# USB_Audio.net
KiCad netlist of a schematic drawn in Altium Designer
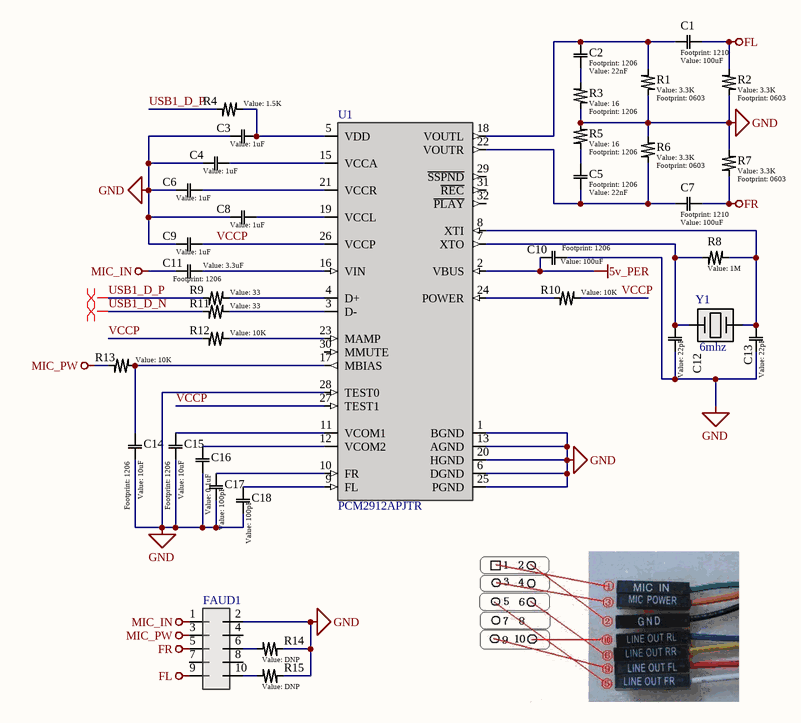
[diagram p0: USB_Audio.SchDoc]

(export (version "E")
  (design (tool "Eeschema 10.0.6"))
  (components
    (comp (ref "C1")
      (value "100uF")
      (footprint "1210")
      (fields
        (field (name "VOLTAGE") ">10V")
        (field (name "TOLERANCE") "10%")
        (field (name "Comment") "Generic Capacitor")
      )
      (libsource (lib "Capacitors") (part "Generic Capacitor"))
    )
    (comp (ref "C2")
      (value "22nF")
      (footprint "1206")
      (fields
        (field (name "VOLTAGE") ">10V")
        (field (name "TOLERANCE") "10%")
        (field (name "Comment") "Generic Capacitor")
      )
      (libsource (lib "Capacitors") (part "Generic Capacitor"))
    )
    (comp (ref "C3")
      (value "1uF")
      (footprint "0603")
      (fields
        (field (name "VOLTAGE") ">10V")
        (field (name "TOLERANCE") "10%")
        (field (name "Comment") "Generic Capacitor")
      )
      (libsource (lib "Capacitors") (part "Generic Capacitor"))
    )
    (comp (ref "C4")
      (value "1uF")
      (footprint "0603")
      (fields
        (field (name "VOLTAGE") ">10V")
        (field (name "TOLERANCE") "10%")
        (field (name "Comment") "Generic Capacitor")
      )
      (libsource (lib "Capacitors") (part "Generic Capacitor"))
    )
    (comp (ref "C5")
      (value "22nF")
      (footprint "1206")
      (fields
        (field (name "VOLTAGE") ">10V")
        (field (name "TOLERANCE") "10%")
        (field (name "Comment") "Generic Capacitor")
      )
      (libsource (lib "Capacitors") (part "Generic Capacitor"))
    )
    (comp (ref "C6")
      (value "1uF")
      (footprint "0603")
      (fields
        (field (name "VOLTAGE") ">10V")
        (field (name "TOLERANCE") "10%")
        (field (name "Comment") "Generic Capacitor")
      )
      (libsource (lib "Capacitors") (part "Generic Capacitor"))
    )
    (comp (ref "C7")
      (value "100uF")
      (footprint "1210")
      (fields
        (field (name "VOLTAGE") ">10V")
        (field (name "TOLERANCE") "10%")
        (field (name "Comment") "Generic Capacitor")
      )
      (libsource (lib "Capacitors") (part "Generic Capacitor"))
    )
    (comp (ref "C8")
      (value "1uF")
      (footprint "0603")
      (fields
        (field (name "VOLTAGE") ">10V")
        (field (name "TOLERANCE") "10%")
        (field (name "Comment") "Generic Capacitor")
      )
      (libsource (lib "Capacitors") (part "Generic Capacitor"))
    )
    (comp (ref "C9")
      (value "1uF")
      (footprint "0603")
      (fields
        (field (name "VOLTAGE") ">10V")
        (field (name "TOLERANCE") "10%")
        (field (name "Comment") "Generic Capacitor")
      )
      (libsource (lib "Capacitors") (part "Generic Capacitor"))
    )
    (comp (ref "C10")
      (value "100uF")
      (footprint "1206")
      (fields
        (field (name "VOLTAGE") ">10V")
        (field (name "TOLERANCE") "10%")
        (field (name "Comment") "Generic Capacitor")
      )
      (libsource (lib "Capacitors") (part "Generic Capacitor"))
    )
    (comp (ref "C11")
      (value "3.3uF")
      (footprint "1206")
      (fields
        (field (name "VOLTAGE") ">10V")
        (field (name "TOLERANCE") "10%")
        (field (name "Comment") "Generic Capacitor")
      )
      (libsource (lib "Capacitors") (part "Generic Capacitor"))
    )
    (comp (ref "C12")
      (value "22pF")
      (footprint "0603")
      (fields
        (field (name "VOLTAGE") ">10V")
        (field (name "TOLERANCE") "10%")
        (field (name "Comment") "Generic Capacitor")
      )
      (libsource (lib "Capacitors") (part "Generic Capacitor"))
    )
    (comp (ref "C13")
      (value "22pF")
      (footprint "0603")
      (fields
        (field (name "VOLTAGE") ">10V")
        (field (name "TOLERANCE") "10%")
        (field (name "Comment") "Generic Capacitor")
      )
      (libsource (lib "Capacitors") (part "Generic Capacitor"))
    )
    (comp (ref "C14")
      (value "10uF")
      (footprint "1206")
      (fields
        (field (name "VOLTAGE") ">10V")
        (field (name "TOLERANCE") "10%")
        (field (name "Comment") "Generic Capacitor")
      )
      (libsource (lib "Capacitors") (part "Generic Capacitor"))
    )
    (comp (ref "C15")
      (value "10uF")
      (footprint "1206")
      (fields
        (field (name "VOLTAGE") ">10V")
        (field (name "TOLERANCE") "10%")
        (field (name "Comment") "Generic Capacitor")
      )
      (libsource (lib "Capacitors") (part "Generic Capacitor"))
    )
    (comp (ref "C16")
      (value "0.1uF")
      (footprint "0603")
      (fields
        (field (name "VOLTAGE") ">10V")
        (field (name "TOLERANCE") "10%")
        (field (name "Comment") "Generic Capacitor")
      )
      (libsource (lib "Capacitors") (part "Generic Capacitor"))
    )
    (comp (ref "C17")
      (value "100pF")
      (footprint "0603")
      (fields
        (field (name "VOLTAGE") ">10V")
        (field (name "TOLERANCE") "10%")
        (field (name "Comment") "Generic Capacitor")
      )
      (libsource (lib "Capacitors") (part "Generic Capacitor"))
    )
    (comp (ref "C18")
      (value "100pF")
      (footprint "0603")
      (fields
        (field (name "VOLTAGE") ">10V")
        (field (name "TOLERANCE") "10%")
        (field (name "Comment") "Generic Capacitor")
      )
      (libsource (lib "Capacitors") (part "Generic Capacitor"))
    )
    (comp (ref "FAUD1")
      (value "10pinMobo")
      (footprint "10pinMobo")
      (description "10pin motherboard jack")
      (libsource (lib "Connectors") (part "10pinMobo"))
    )
    (comp (ref "R1")
      (value "3.3K")
      (footprint "0603")
      (fields
        (field (name "TOLERANCE") "1%")
        (field (name "POWER") "1/10W")
        (field (name "Comment") "Generic Resistor")
      )
      (libsource (lib "Resistors") (part "Generic Resistor"))
    )
    (comp (ref "R2")
      (value "3.3K")
      (footprint "0603")
      (fields
        (field (name "TOLERANCE") "1%")
        (field (name "POWER") "1/10W")
        (field (name "Comment") "Generic Resistor")
      )
      (libsource (lib "Resistors") (part "Generic Resistor"))
    )
    (comp (ref "R3")
      (value "16")
      (footprint "1206")
      (fields
        (field (name "TOLERANCE") "1%")
        (field (name "POWER") "1/10W")
        (field (name "Comment") "Generic Resistor")
      )
      (libsource (lib "Resistors") (part "Generic Resistor"))
    )
    (comp (ref "R4")
      (value "1.5K")
      (footprint "0603")
      (fields
        (field (name "TOLERANCE") "1%")
        (field (name "POWER") "1/10W")
        (field (name "Comment") "Generic Resistor")
      )
      (libsource (lib "Resistors") (part "Generic Resistor"))
    )
    (comp (ref "R5")
      (value "16")
      (footprint "1206")
      (fields
        (field (name "TOLERANCE") "1%")
        (field (name "POWER") "1/10W")
        (field (name "Comment") "Generic Resistor")
      )
      (libsource (lib "Resistors") (part "Generic Resistor"))
    )
    (comp (ref "R6")
      (value "3.3K")
      (footprint "0603")
      (fields
        (field (name "TOLERANCE") "1%")
        (field (name "POWER") "1/10W")
        (field (name "Comment") "Generic Resistor")
      )
      (libsource (lib "Resistors") (part "Generic Resistor"))
    )
    (comp (ref "R7")
      (value "3.3K")
      (footprint "0603")
      (fields
        (field (name "TOLERANCE") "1%")
        (field (name "POWER") "1/10W")
        (field (name "Comment") "Generic Resistor")
      )
      (libsource (lib "Resistors") (part "Generic Resistor"))
    )
    (comp (ref "R8")
      (value "1M")
      (footprint "0603")
      (fields
        (field (name "TOLERANCE") "1%")
        (field (name "POWER") "1/10W")
        (field (name "Comment") "Generic Resistor")
      )
      (libsource (lib "Resistors") (part "Generic Resistor"))
    )
    (comp (ref "R9")
      (value "33")
      (footprint "0603")
      (fields
        (field (name "TOLERANCE") "1%")
        (field (name "POWER") "1/10W")
        (field (name "Comment") "Generic Resistor")
      )
      (libsource (lib "Resistors") (part "Generic Resistor"))
    )
    (comp (ref "R10")
      (value "10K")
      (footprint "0603")
      (fields
        (field (name "TOLERANCE") "1%")
        (field (name "POWER") "1/10W")
        (field (name "Comment") "Generic Resistor")
      )
      (libsource (lib "Resistors") (part "Generic Resistor"))
    )
    (comp (ref "R11")
      (value "33")
      (footprint "0603")
      (fields
        (field (name "TOLERANCE") "1%")
        (field (name "POWER") "1/10W")
        (field (name "Comment") "Generic Resistor")
      )
      (libsource (lib "Resistors") (part "Generic Resistor"))
    )
    (comp (ref "R12")
      (value "10K")
      (footprint "0603")
      (fields
        (field (name "TOLERANCE") "1%")
        (field (name "POWER") "1/10W")
        (field (name "Comment") "Generic Resistor")
      )
      (libsource (lib "Resistors") (part "Generic Resistor"))
    )
    (comp (ref "R13")
      (value "10K")
      (footprint "0603")
      (fields
        (field (name "TOLERANCE") "1%")
        (field (name "POWER") "1/10W")
        (field (name "Comment") "Generic Resistor")
      )
      (libsource (lib "Resistors") (part "Generic Resistor"))
    )
    (comp (ref "R14")
      (value "DNP")
      (footprint "0603")
      (fields
        (field (name "TOLERANCE") "1%")
        (field (name "POWER") "1/10W")
        (field (name "Comment") "Generic Resistor")
      )
      (libsource (lib "Resistors") (part "Generic Resistor"))
    )
    (comp (ref "R15")
      (value "DNP")
      (footprint "0603")
      (fields
        (field (name "TOLERANCE") "1%")
        (field (name "POWER") "1/10W")
        (field (name "Comment") "Generic Resistor")
      )
      (libsource (lib "Resistors") (part "Generic Resistor"))
    )
    (comp (ref "U1")
      (value "PCM2912APJTR")
      (footprint "32-TQFP")
      (fields (field (name "MF") "Texas Instruments"))
      (libsource (lib "Misc ICs") (part "PCM2912APJTR"))
    )
    (comp (ref "Y1")
      (value "6mhz")
      (footprint "HC-49S-SMD")
      (description "6MHz Surface Mount Crystal 20pF ±20ppm ±30ppm HC-49S-SMD Crystals")
      (libsource (lib "Clock ICs") (part "H6OEL89CSC-SUGYLC-6M"))
    )
  )
  (nets
    (net (code "1") (name "/USB1_D_N") (class "Default")
      (node (ref "R11") (pin "2") (pinfunction "2_2") (pintype "passive"))
    )
    (net (code "2") (name "/USB1_D_P") (class "Default")
      (node (ref "R4") (pin "2") (pinfunction "2_2") (pintype "passive"))
      (node (ref "R9") (pin "2") (pinfunction "2_2") (pintype "passive"))
    )
    (net (code "3") (name "/VCCP") (class "Default")
      (node (ref "C9") (pin "2") (pinfunction "2_2") (pintype "passive"))
      (node (ref "R10") (pin "1") (pinfunction "1_1") (pintype "passive"))
      (node (ref "R12") (pin "2") (pinfunction "2_2") (pintype "passive"))
      (node (ref "U1") (pin "26") (pinfunction "VCCP_26") (pintype "power_in"))
      (node (ref "U1") (pin "27") (pinfunction "TEST1_27") (pintype "input"))
    )
    (net (code "4") (name "5v_PER") (class "Default")
      (node (ref "C10") (pin "1") (pinfunction "1_1") (pintype "passive"))
      (node (ref "U1") (pin "2") (pinfunction "VBUS_2") (pintype "input"))
    )
    (net (code "5") (name "FL") (class "Default")
      (node (ref "C1") (pin "1") (pinfunction "1_1") (pintype "passive"))
      (node (ref "FAUD1") (pin "9") (pinfunction "9_9") (pintype "passive"))
      (node (ref "R2") (pin "2") (pinfunction "2_2") (pintype "passive"))
    )
    (net (code "6") (name "FR") (class "Default")
      (node (ref "C7") (pin "1") (pinfunction "1_1") (pintype "passive"))
      (node (ref "FAUD1") (pin "5") (pinfunction "5_5") (pintype "passive"))
      (node (ref "R7") (pin "2") (pinfunction "2_2") (pintype "passive"))
    )
    (net (code "7") (name "GND") (class "Default")
      (node (ref "C10") (pin "2") (pinfunction "2_2") (pintype "passive"))
      (node (ref "C12") (pin "2") (pinfunction "2_2") (pintype "passive"))
      (node (ref "C13") (pin "2") (pinfunction "2_2") (pintype "passive"))
      (node (ref "C14") (pin "2") (pinfunction "2_2") (pintype "passive"))
      (node (ref "C15") (pin "2") (pinfunction "2_2") (pintype "passive"))
      (node (ref "C16") (pin "2") (pinfunction "2_2") (pintype "passive"))
      (node (ref "C17") (pin "2") (pinfunction "2_2") (pintype "passive"))
      (node (ref "C18") (pin "2") (pinfunction "2_2") (pintype "passive"))
      (node (ref "C3") (pin "1") (pinfunction "1_1") (pintype "passive"))
      (node (ref "C4") (pin "1") (pinfunction "1_1") (pintype "passive"))
      (node (ref "C6") (pin "1") (pinfunction "1_1") (pintype "passive"))
      (node (ref "C8") (pin "1") (pinfunction "1_1") (pintype "passive"))
      (node (ref "C9") (pin "1") (pinfunction "1_1") (pintype "passive"))
      (node (ref "FAUD1") (pin "2") (pinfunction "2_2") (pintype "passive"))
      (node (ref "R1") (pin "1") (pinfunction "1_1") (pintype "passive"))
      (node (ref "R14") (pin "1") (pinfunction "1_1") (pintype "passive"))
      (node (ref "R15") (pin "1") (pinfunction "1_1") (pintype "passive"))
      (node (ref "R2") (pin "1") (pinfunction "1_1") (pintype "passive"))
      (node (ref "R3") (pin "1") (pinfunction "1_1") (pintype "passive"))
      (node (ref "R5") (pin "1") (pinfunction "1_1") (pintype "passive"))
      (node (ref "R6") (pin "1") (pinfunction "1_1") (pintype "passive"))
      (node (ref "R7") (pin "1") (pinfunction "1_1") (pintype "passive"))
      (node (ref "U1") (pin "1") (pinfunction "BGND_1") (pintype "power_in"))
      (node (ref "U1") (pin "13") (pinfunction "AGND_13") (pintype "power_in"))
      (node (ref "U1") (pin "20") (pinfunction "HGND_20") (pintype "power_in"))
      (node (ref "U1") (pin "25") (pinfunction "PGND_25") (pintype "power_in"))
      (node (ref "U1") (pin "28") (pinfunction "TEST0_28") (pintype "input"))
      (node (ref "U1") (pin "6") (pinfunction "DGND_6") (pintype "power_in"))
    )
    (net (code "8") (name "MIC_IN") (class "Default")
      (node (ref "C11") (pin "2") (pinfunction "2_2") (pintype "passive"))
      (node (ref "FAUD1") (pin "1") (pinfunction "1_1") (pintype "passive"))
    )
    (net (code "9") (name "MIC_PW") (class "Default")
      (node (ref "FAUD1") (pin "3") (pinfunction "3_3") (pintype "passive"))
      (node (ref "R13") (pin "2") (pinfunction "2_2") (pintype "passive"))
    )
    (net (code "10") (name "Net-(C2-Pad2)") (class "Default")
      (node (ref "C2") (pin "2") (pinfunction "2_2") (pintype "passive"))
      (node (ref "R3") (pin "2") (pinfunction "2_2") (pintype "passive"))
    )
    (net (code "11") (name "Net-(C5-Pad2)") (class "Default")
      (node (ref "C5") (pin "2") (pinfunction "2_2") (pintype "passive"))
      (node (ref "R5") (pin "2") (pinfunction "2_2") (pintype "passive"))
    )
    (net (code "12") (name "Net-(FAUD1-Pad6)") (class "Default")
      (node (ref "FAUD1") (pin "6") (pinfunction "6_6") (pintype "passive"))
      (node (ref "R14") (pin "2") (pinfunction "2_2") (pintype "passive"))
    )
    (net (code "13") (name "Net-(FAUD1-Pad10)") (class "Default")
      (node (ref "FAUD1") (pin "10") (pinfunction "10_10") (pintype "passive"))
      (node (ref "R15") (pin "2") (pinfunction "2_2") (pintype "passive"))
    )
    (net (code "14") (name "Net-(U1-D+)") (class "Default")
      (node (ref "R9") (pin "1") (pinfunction "1_1") (pintype "passive"))
      (node (ref "U1") (pin "4") (pinfunction "D+_4") (pintype "bidirectional"))
    )
    (net (code "15") (name "Net-(U1-D-)") (class "Default")
      (node (ref "R11") (pin "1") (pinfunction "1_1") (pintype "passive"))
      (node (ref "U1") (pin "3") (pinfunction "D-_3") (pintype "bidirectional"))
    )
    (net (code "16") (name "Net-(U1-FL)") (class "Default")
      (node (ref "C18") (pin "1") (pinfunction "1_1") (pintype "passive"))
      (node (ref "U1") (pin "9") (pinfunction "FL_9") (pintype "input"))
    )
    (net (code "17") (name "Net-(U1-FR)") (class "Default")
      (node (ref "C17") (pin "1") (pinfunction "1_1") (pintype "passive"))
      (node (ref "U1") (pin "10") (pinfunction "FR_10") (pintype "input"))
    )
    (net (code "18") (name "Net-(U1-MAMP)") (class "Default")
      (node (ref "R12") (pin "1") (pinfunction "1_1") (pintype "passive"))
      (node (ref "U1") (pin "23") (pinfunction "MAMP_23") (pintype "input"))
    )
    (net (code "19") (name "Net-(U1-MBIAS)") (class "Default")
      (node (ref "C14") (pin "1") (pinfunction "1_1") (pintype "passive"))
      (node (ref "R13") (pin "1") (pinfunction "1_1") (pintype "passive"))
      (node (ref "U1") (pin "17") (pinfunction "MBIAS_17") (pintype "output"))
    )
    (net (code "20") (name "Net-(U1-POWER)") (class "Default")
      (node (ref "R10") (pin "2") (pinfunction "2_2") (pintype "passive"))
      (node (ref "U1") (pin "24") (pinfunction "POWER_24") (pintype "input"))
    )
    (net (code "21") (name "Net-(U1-VCCA)") (class "Default")
      (node (ref "C4") (pin "2") (pinfunction "2_2") (pintype "passive"))
      (node (ref "U1") (pin "15") (pinfunction "VCCA_15") (pintype "power_in"))
    )
    (net (code "22") (name "Net-(U1-VCCL)") (class "Default")
      (node (ref "C8") (pin "2") (pinfunction "2_2") (pintype "passive"))
      (node (ref "U1") (pin "19") (pinfunction "VCCL_19") (pintype "power_in"))
    )
    (net (code "23") (name "Net-(U1-VCCR)") (class "Default")
      (node (ref "C6") (pin "2") (pinfunction "2_2") (pintype "passive"))
      (node (ref "U1") (pin "21") (pinfunction "VCCR_21") (pintype "power_in"))
    )
    (net (code "24") (name "Net-(U1-VCOM1)") (class "Default")
      (node (ref "C15") (pin "1") (pinfunction "1_1") (pintype "passive"))
      (node (ref "U1") (pin "11") (pinfunction "VCOM1_11") (pintype "power_in"))
    )
    (net (code "25") (name "Net-(U1-VCOM2)") (class "Default")
      (node (ref "C16") (pin "1") (pinfunction "1_1") (pintype "passive"))
      (node (ref "U1") (pin "12") (pinfunction "VCOM2_12") (pintype "power_in"))
    )
    (net (code "26") (name "Net-(U1-VDD)") (class "Default")
      (node (ref "C3") (pin "2") (pinfunction "2_2") (pintype "passive"))
      (node (ref "R4") (pin "1") (pinfunction "1_1") (pintype "passive"))
      (node (ref "U1") (pin "5") (pinfunction "VDD_5") (pintype "power_in"))
    )
    (net (code "27") (name "Net-(U1-VIN)") (class "Default")
      (node (ref "C11") (pin "1") (pinfunction "1_1") (pintype "passive"))
      (node (ref "U1") (pin "16") (pinfunction "VIN_16") (pintype "input"))
    )
    (net (code "28") (name "Net-(U1-VOUTL)") (class "Default")
      (node (ref "C1") (pin "2") (pinfunction "2_2") (pintype "passive"))
      (node (ref "C2") (pin "1") (pinfunction "1_1") (pintype "passive"))
      (node (ref "R1") (pin "2") (pinfunction "2_2") (pintype "passive"))
      (node (ref "U1") (pin "18") (pinfunction "VOUTL_18") (pintype "output"))
    )
    (net (code "29") (name "Net-(U1-VOUTR)") (class "Default")
      (node (ref "C5") (pin "1") (pinfunction "1_1") (pintype "passive"))
      (node (ref "C7") (pin "2") (pinfunction "2_2") (pintype "passive"))
      (node (ref "R6") (pin "2") (pinfunction "2_2") (pintype "passive"))
      (node (ref "U1") (pin "22") (pinfunction "VOUTR_22") (pintype "output"))
    )
    (net (code "30") (name "Net-(U1-XTI)") (class "Default")
      (node (ref "C13") (pin "1") (pinfunction "1_1") (pintype "passive"))
      (node (ref "R8") (pin "2") (pinfunction "2_2") (pintype "passive"))
      (node (ref "U1") (pin "8") (pinfunction "XTI_8") (pintype "input"))
      (node (ref "Y1") (pin "2") (pintype "passive"))
    )
    (net (code "31") (name "Net-(U1-XTO)") (class "Default")
      (node (ref "C12") (pin "1") (pinfunction "1_1") (pintype "passive"))
      (node (ref "R8") (pin "1") (pinfunction "1_1") (pintype "passive"))
      (node (ref "U1") (pin "7") (pinfunction "XTO_7") (pintype "output"))
      (node (ref "Y1") (pin "1") (pintype "passive"))
    )
    (net (code "32") (name "unconnected-(FAUD1-Pad4)") (class "Default")
      (node (ref "FAUD1") (pin "4") (pinfunction "4_4") (pintype "passive"))
    )
    (net (code "33") (name "unconnected-(FAUD1-Pad7)") (class "Default")
      (node (ref "FAUD1") (pin "7") (pinfunction "7_7") (pintype "passive"))
    )
    (net (code "34") (name "unconnected-(FAUD1-Pad8)") (class "Default")
      (node (ref "FAUD1") (pin "8") (pinfunction "8_8") (pintype "passive"))
    )
    (net (code "35") (name "unconnected-(U1-MMUTE-Pad30)") (class "Default")
      (node (ref "U1") (pin "30") (pinfunction "MMUTE_30") (pintype "input"))
    )
    (net (code "36") (name "unconnected-(U1-~{PLAY}-Pad32)") (class "Default")
      (node (ref "U1") (pin "32") (pinfunction "~{PLAY}_32") (pintype "output"))
    )
    (net (code "37") (name "unconnected-(U1-~{REC}-Pad31)") (class "Default")
      (node (ref "U1") (pin "31") (pinfunction "~{REC}_31") (pintype "output"))
    )
    (net (code "38") (name "unconnected-(U1-~{SSPND}-Pad29)") (class "Default")
      (node (ref "U1") (pin "29") (pinfunction "~{SSPND}_29") (pintype "output"))
    )
  )
)
